# SCH_business-card_2024-05-25.net
KiCad netlist of a schematic drawn in EasyEDA
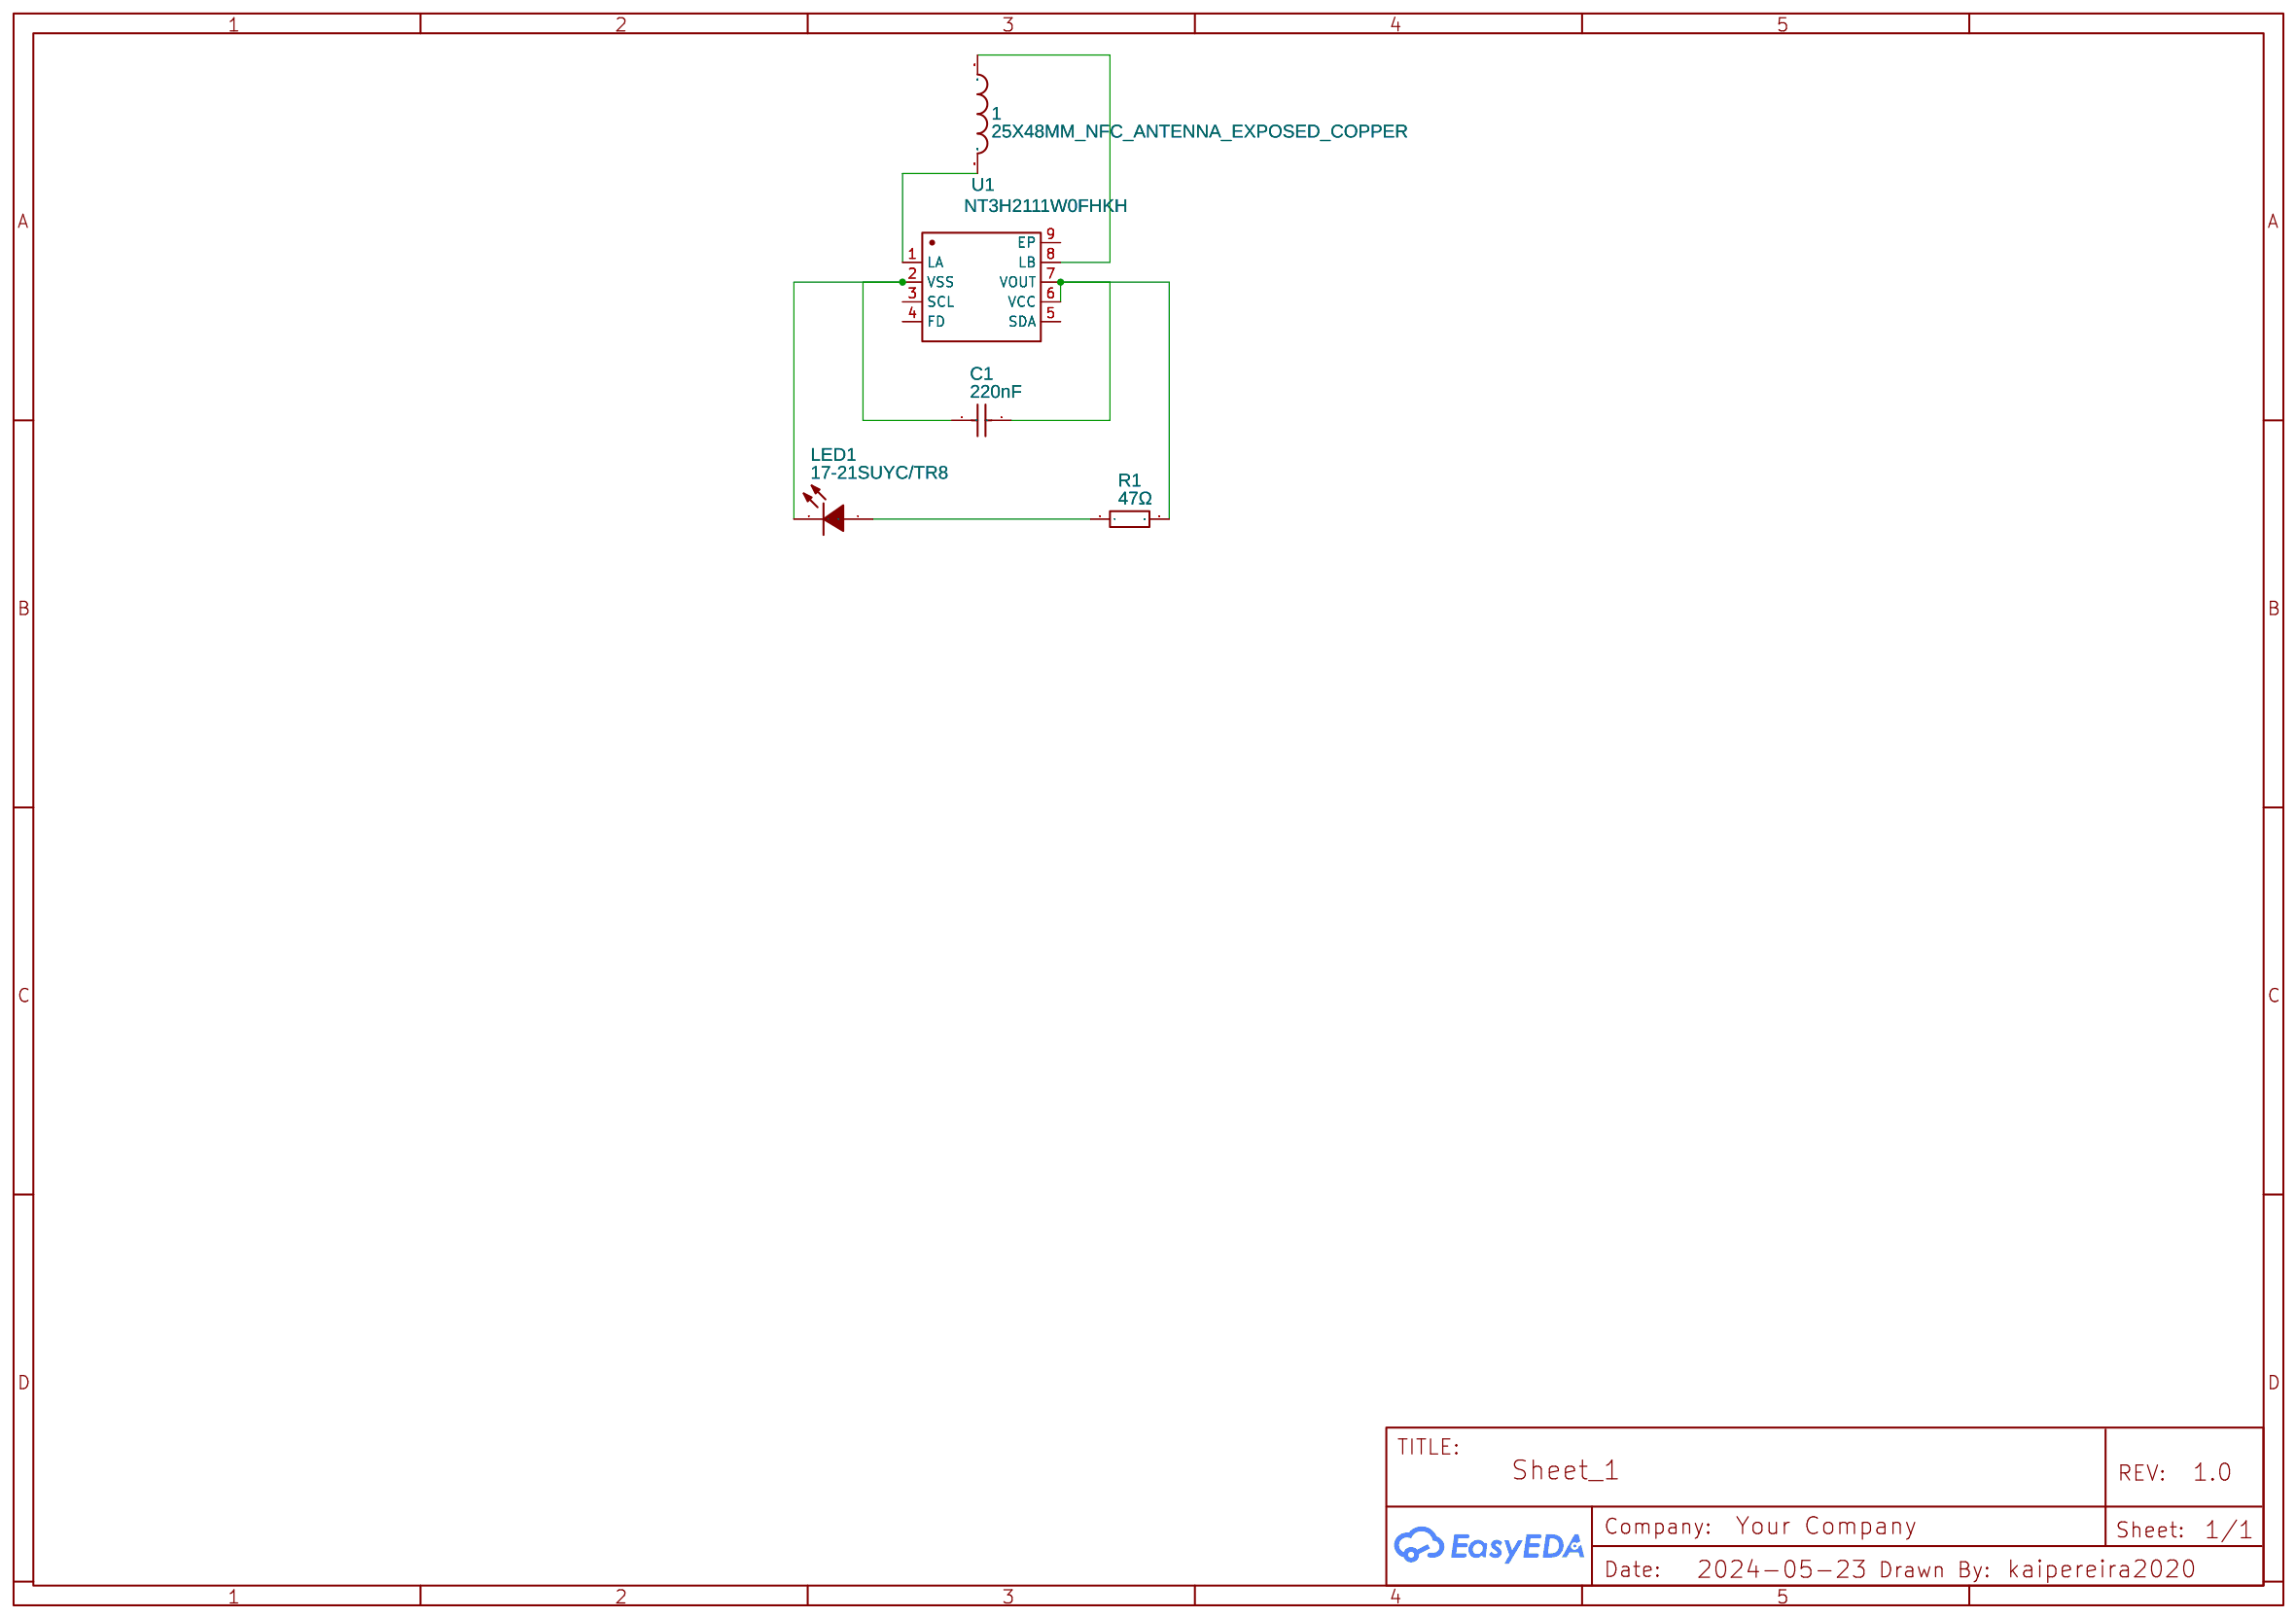
[diagram p0: schematic sheet]

(export (version "E")
  (design (tool "Eeschema 10.0.6"))
  (components
    (comp (ref "1")
      (value "25X48MM_NFC_ANTENNA_EXPOSED_COPPER")
      (libsource (lib "") (part "25X48MM_NFC_ANTENNA_EXPOSED_COPPER"))
    )
    (comp (ref "C1")
      (value "220nF")
      (fields
        (field (name "Manufacturer Part") "CL10B224KA8NNNC")
        (field (name "Manufacturer") "SAMSUNG(三星)")
      )
      (libsource (lib "") (part "CL10B224KA8NNNC"))
    )
    (comp (ref "LED1")
      (value "17-21SUYC/TR8")
      (fields (field (name "Manufacturer Part") "KT-0805黄灯") (field (name "Manufacturer") "KENTO"))
      (libsource (lib "") (part "17-21SUYC/TR8"))
    )
    (comp (ref "R1")
      (value "47Ω")
      (fields
        (field (name "Manufacturer Part") "0603WAF470JT5E")
        (field (name "Manufacturer") "UNI-ROYAL(厚声)")
      )
      (libsource (lib "") (part "0603WAF470JT5E"))
    )
    (comp (ref "U1")
      (value "NT3H2111W0FHKH")
      (fields (field (name "Manufacturer") "NXP(恩智浦)"))
      (libsource (lib "") (part "NT3H2111W0FHKH"))
    )
  )
  (nets
    (net (code "1") (name "Net-(LED1-+)") (class "Default")
      (node (ref "LED1") (pin "1") (pinfunction "+_1") (pintype "unspecified"))
      (node (ref "R1") (pin "1") (pinfunction "1_1") (pintype "input"))
    )
    (net (code "2") (name "Net-(LED1--)") (class "Default")
      (node (ref "C1") (pin "1") (pinfunction "1_1") (pintype "input"))
      (node (ref "LED1") (pin "2") (pinfunction "-_2") (pintype "unspecified"))
      (node (ref "U1") (pin "2") (pinfunction "VSS_2") (pintype "unspecified"))
    )
    (net (code "3") (name "Net-(U1-LA)") (class "Default")
      (node (ref "1") (pin "P$2") (pinfunction "P$2_P$2") (pintype "bidirectional"))
      (node (ref "U1") (pin "1") (pinfunction "LA_1") (pintype "unspecified"))
    )
    (net (code "4") (name "Net-(U1-LB)") (class "Default")
      (node (ref "1") (pin "P$1") (pinfunction "P$1_P$1") (pintype "bidirectional"))
      (node (ref "U1") (pin "8") (pinfunction "LB_8") (pintype "unspecified"))
    )
    (net (code "5") (name "Net-(U1-VCC)") (class "Default")
      (node (ref "C1") (pin "2") (pinfunction "2_2") (pintype "input"))
      (node (ref "R1") (pin "2") (pinfunction "2_2") (pintype "input"))
      (node (ref "U1") (pin "6") (pinfunction "VCC_6") (pintype "unspecified"))
      (node (ref "U1") (pin "7") (pinfunction "VOUT_7") (pintype "unspecified"))
    )
    (net (code "6") (name "unconnected-(U1-EP-Pad9)") (class "Default")
      (node (ref "U1") (pin "9") (pinfunction "EP_9") (pintype "unspecified"))
    )
    (net (code "7") (name "unconnected-(U1-FD-Pad4)") (class "Default")
      (node (ref "U1") (pin "4") (pinfunction "FD_4") (pintype "unspecified"))
    )
    (net (code "8") (name "unconnected-(U1-SCL-Pad3)") (class "Default")
      (node (ref "U1") (pin "3") (pinfunction "SCL_3") (pintype "unspecified"))
    )
    (net (code "9") (name "unconnected-(U1-SDA-Pad5)") (class "Default")
      (node (ref "U1") (pin "5") (pinfunction "SDA_5") (pintype "unspecified"))
    )
  )
)
